# resistive-probe-adapter.net
KiCad netlist of a schematic drawn in EAGLE
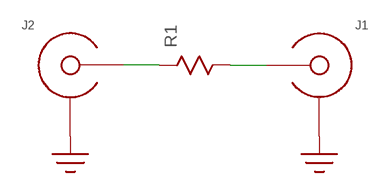
[diagram p0: schematic, sheet 1]

(export (version "E")
  (design (tool "Eeschema 10.0.6"))
  (components
    (comp (ref "J1")
      (value "SMA-EDGE-LAUNCH4020_TAPER")
      (footprint "eagle-import:SMA_EDGE_LAUNCH_2L_4020_TAPER")
      (libsource (lib "eagle-import") (part "SMA-EDGE-LAUNCH4020_TAPER"))
    )
    (comp (ref "J2")
      (value "SMA-EDGE-LAUNCH4020_TAPER")
      (footprint "eagle-import:SMA_EDGE_LAUNCH_2L_4020_TAPER")
      (libsource (lib "eagle-import") (part "SMA-EDGE-LAUNCH4020_TAPER"))
    )
    (comp (ref "R1")
      (value "R0603")
      (footprint "eagle-import:R0603")
      (libsource (lib "eagle-import") (part "R0603"))
    )
  )
  (nets
    (net (code "1") (name "GND") (class "Default")
      (node (ref "J1") (pin "BOTTOM_GND") (pinfunction "SHIELD_BOTTOM_GND") (pintype "bidirectional"))
      (node (ref "J1") (pin "GND@1") (pinfunction "SHIELD_GND@1") (pintype "bidirectional"))
      (node (ref "J1") (pin "GND@14") (pinfunction "SHIELD_GND@14") (pintype "bidirectional"))
      (node (ref "J1") (pin "GND@15") (pinfunction "SHIELD_GND@15") (pintype "bidirectional"))
      (node (ref "J1") (pin "GND@16") (pinfunction "SHIELD_GND@16") (pintype "bidirectional"))
      (node (ref "J1") (pin "GND@17") (pinfunction "SHIELD_GND@17") (pintype "bidirectional"))
      (node (ref "J1") (pin "GND@2") (pinfunction "SHIELD_GND@2") (pintype "bidirectional"))
      (node (ref "J1") (pin "GND@3") (pinfunction "SHIELD_GND@3") (pintype "bidirectional"))
      (node (ref "J1") (pin "GND@4") (pinfunction "SHIELD_GND@4") (pintype "bidirectional"))
      (node (ref "J1") (pin "GND@5") (pinfunction "SHIELD_GND@5") (pintype "bidirectional"))
      (node (ref "J1") (pin "GND@6") (pinfunction "SHIELD_GND@6") (pintype "bidirectional"))
      (node (ref "J1") (pin "GND@7") (pinfunction "SHIELD_GND@7") (pintype "bidirectional"))
      (node (ref "J1") (pin "GND@8") (pinfunction "SHIELD_GND@8") (pintype "bidirectional"))
      (node (ref "J1") (pin "GND_PAD1") (pinfunction "SHIELD_GND_PAD1") (pintype "bidirectional"))
      (node (ref "J1") (pin "GND_PAD2") (pinfunction "SHIELD_GND_PAD2") (pintype "bidirectional"))
      (node (ref "J1") (pin "P$1") (pinfunction "SHIELD_P$1") (pintype "bidirectional"))
      (node (ref "J1") (pin "P$2") (pinfunction "SHIELD_P$2") (pintype "bidirectional"))
      (node (ref "J2") (pin "BOTTOM_GND") (pinfunction "SHIELD_BOTTOM_GND") (pintype "bidirectional"))
      (node (ref "J2") (pin "GND@1") (pinfunction "SHIELD_GND@1") (pintype "bidirectional"))
      (node (ref "J2") (pin "GND@14") (pinfunction "SHIELD_GND@14") (pintype "bidirectional"))
      (node (ref "J2") (pin "GND@15") (pinfunction "SHIELD_GND@15") (pintype "bidirectional"))
      (node (ref "J2") (pin "GND@16") (pinfunction "SHIELD_GND@16") (pintype "bidirectional"))
      (node (ref "J2") (pin "GND@17") (pinfunction "SHIELD_GND@17") (pintype "bidirectional"))
      (node (ref "J2") (pin "GND@2") (pinfunction "SHIELD_GND@2") (pintype "bidirectional"))
      (node (ref "J2") (pin "GND@3") (pinfunction "SHIELD_GND@3") (pintype "bidirectional"))
      (node (ref "J2") (pin "GND@4") (pinfunction "SHIELD_GND@4") (pintype "bidirectional"))
      (node (ref "J2") (pin "GND@5") (pinfunction "SHIELD_GND@5") (pintype "bidirectional"))
      (node (ref "J2") (pin "GND@6") (pinfunction "SHIELD_GND@6") (pintype "bidirectional"))
      (node (ref "J2") (pin "GND@7") (pinfunction "SHIELD_GND@7") (pintype "bidirectional"))
      (node (ref "J2") (pin "GND@8") (pinfunction "SHIELD_GND@8") (pintype "bidirectional"))
      (node (ref "J2") (pin "GND_PAD1") (pinfunction "SHIELD_GND_PAD1") (pintype "bidirectional"))
      (node (ref "J2") (pin "GND_PAD2") (pinfunction "SHIELD_GND_PAD2") (pintype "bidirectional"))
      (node (ref "J2") (pin "P$1") (pinfunction "SHIELD_P$1") (pintype "bidirectional"))
      (node (ref "J2") (pin "P$2") (pinfunction "SHIELD_P$2") (pintype "bidirectional"))
    )
    (net (code "2") (name "Net-(J1-CENTER)") (class "Default")
      (node (ref "J1") (pin "CENTER@1") (pinfunction "CENTER_CENTER@1") (pintype "bidirectional"))
      (node (ref "R1") (pin "P$2") (pinfunction "P$4_P$2") (pintype "bidirectional"))
    )
    (net (code "3") (name "Net-(J2-CENTER)") (class "Default")
      (node (ref "J2") (pin "CENTER@1") (pinfunction "CENTER_CENTER@1") (pintype "bidirectional"))
      (node (ref "R1") (pin "P$1") (pinfunction "P$3_P$1") (pintype "bidirectional"))
    )
  )
)
